# Switch-220v-HiLink-CC1101-AS07.net
KiCad netlist of a schematic drawn in EAGLE
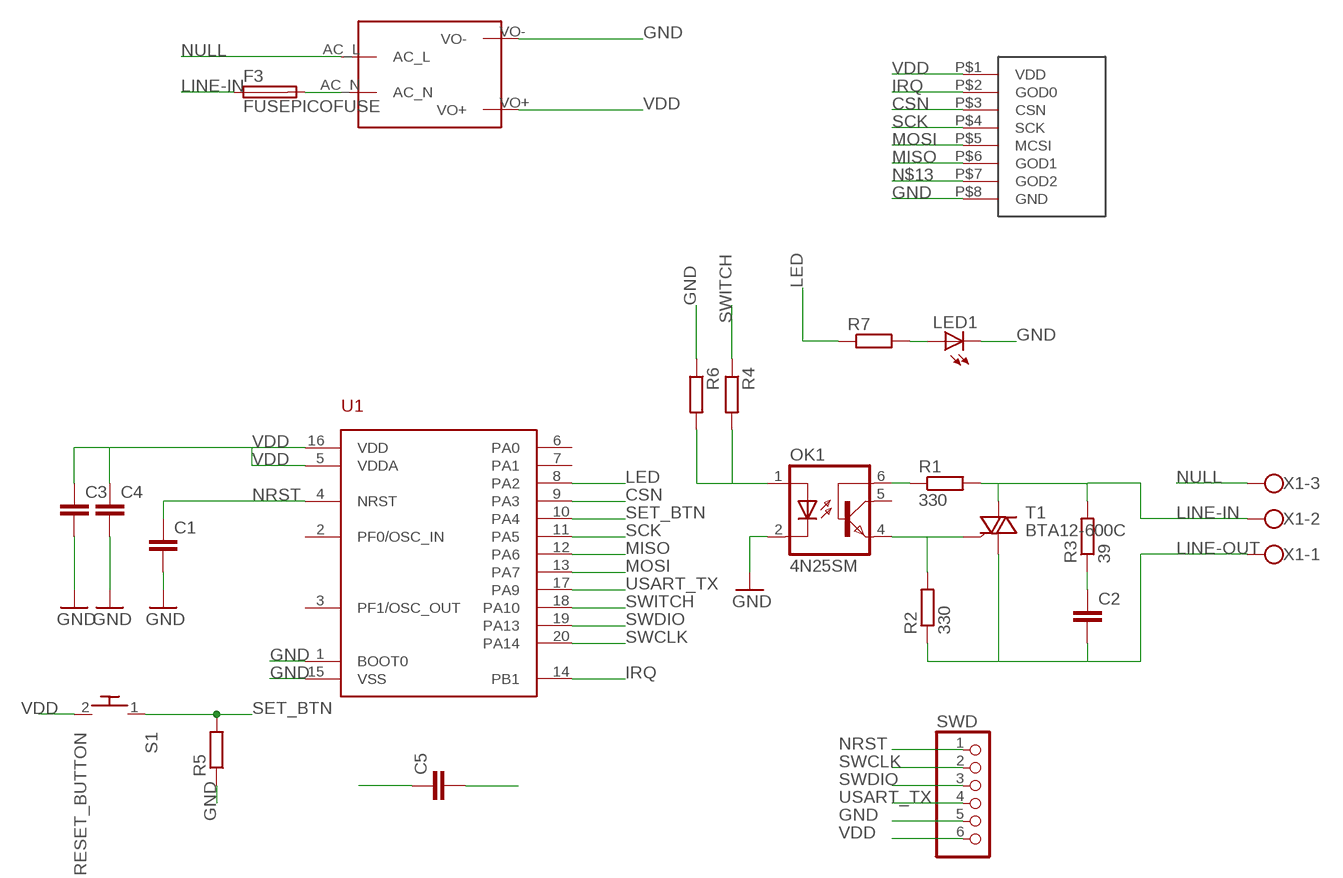
[diagram p0: schematic, sheet 1]

(export (version "E")
  (design (tool "Eeschema 10.0.6"))
  (components
    (comp (ref "C1")
      (value "C-EUC0805")
      (footprint "eagle-import:C0805")
      (libsource (lib "eagle-import") (part "C-EUC0805"))
    )
    (comp (ref "C2")
      (value "C-EU050-025X075")
      (footprint "eagle-import:C050-025X075")
      (libsource (lib "eagle-import") (part "C-EU050-025X075"))
    )
    (comp (ref "C3")
      (value "C-EUC0805")
      (footprint "eagle-import:C0805")
      (libsource (lib "eagle-import") (part "C-EUC0805"))
    )
    (comp (ref "C4")
      (value "C-EUC0805")
      (footprint "eagle-import:C0805")
      (libsource (lib "eagle-import") (part "C-EUC0805"))
    )
    (comp (ref "C5")
      (value "C-EUC0805")
      (footprint "eagle-import:C0805")
      (libsource (lib "eagle-import") (part "C-EUC0805"))
    )
    (comp (ref "F3")
      (value "FUSEPICOFUSE")
      (footprint "eagle-import:PICOFUSE")
      (libsource (lib "eagle-import") (part "FUSEPICOFUSE"))
    )
    (comp (ref "LED1")
      (value "LEDCHIP-LED0805")
      (footprint "eagle-import:CHIP-LED0805")
      (libsource (lib "eagle-import") (part "LEDCHIP-LED0805"))
    )
    (comp (ref "OK1")
      (value "4N25SM")
      (footprint "eagle-import:DIL6-SMD")
      (fields (field (name "MF") "FAIRCHILD SEMICONDUCTOR"))
      (libsource (lib "eagle-import") (part "4N?MS25"))
    )
    (comp (ref "R1")
      (value "330")
      (footprint "eagle-import:0207_2V")
      (libsource (lib "eagle-import") (part "R-EU_0207/2V"))
    )
    (comp (ref "R2")
      (value "330")
      (footprint "eagle-import:0204_7")
      (libsource (lib "eagle-import") (part "R-EU_0204/7"))
    )
    (comp (ref "R3")
      (value "39")
      (footprint "eagle-import:0204_7")
      (libsource (lib "eagle-import") (part "R-EU_0204/7"))
    )
    (comp (ref "R4")
      (value "R-EU_R0805")
      (footprint "eagle-import:R0805")
      (libsource (lib "eagle-import") (part "R-EU_R0805"))
    )
    (comp (ref "R5")
      (value "R-EU_R0805")
      (footprint "eagle-import:R0805")
      (libsource (lib "eagle-import") (part "R-EU_R0805"))
    )
    (comp (ref "R6")
      (value "R-EU_R0805")
      (footprint "eagle-import:R0805")
      (libsource (lib "eagle-import") (part "R-EU_R0805"))
    )
    (comp (ref "R7")
      (value "R-EU_R0805")
      (footprint "eagle-import:R0805")
      (libsource (lib "eagle-import") (part "R-EU_R0805"))
    )
    (comp (ref "S1")
      (value "RESET_BUTTON")
      (footprint "eagle-import:EVQ-PJU05K")
      (libsource (lib "eagle-import") (part "RESET_BUTTON"))
    )
    (comp (ref "SWD")
      (value "PINHD-1X6B")
      (footprint "eagle-import:1X06-BIG")
      (libsource (lib "eagle-import") (part "PINHD-1X6B"))
    )
    (comp (ref "T1")
      (value "BTA12-600C")
      (footprint "eagle-import:TO220DS")
      (libsource (lib "eagle-import") (part "BTA12-600C"))
    )
    (comp (ref "U$2")
      (value "MAINS_CONVERTERS")
      (footprint "eagle-import:HLK-PM01")
      (libsource (lib "eagle-import") (part "MAINS_CONVERTERS"))
    )
    (comp (ref "U$4")
      (value "AS07-M1101SSMD")
      (footprint "eagle-import:AS07-M1101S-SMD")
      (libsource (lib "eagle-import") (part "AS07-M1101SSMD"))
    )
    (comp (ref "U1")
      (value "STM32F030F4")
      (footprint "eagle-import:TSSOP20")
      (libsource (lib "eagle-import") (part "STM32F030F4"))
    )
    (comp (ref "X1")
      (value "W237-103")
      (footprint "eagle-import:W237-103")
      (fields (field (name "MPN") "237-103"))
      (libsource (lib "eagle-import") (part "W237-103"))
    )
  )
  (nets
    (net (code "1") (name "/CSN") (class "Default")
      (node (ref "U$4") (pin "P$3") (pinfunction "CSN_P$3") (pintype "bidirectional"))
      (node (ref "U1") (pin "9") (pinfunction "PA3_9") (pintype "bidirectional"))
    )
    (net (code "2") (name "/IRQ") (class "Default")
      (node (ref "U$4") (pin "P$2") (pinfunction "GOD0_P$2") (pintype "bidirectional"))
      (node (ref "U1") (pin "14") (pinfunction "PB1_14") (pintype "bidirectional"))
    )
    (net (code "3") (name "/LED") (class "Default")
      (node (ref "R7") (pin "1") (pinfunction "1_1") (pintype "passive"))
      (node (ref "U1") (pin "8") (pinfunction "PA2_8") (pintype "bidirectional"))
    )
    (net (code "4") (name "/LINE-IN") (class "Default")
      (node (ref "F3") (pin "1") (pinfunction "1_1") (pintype "passive"))
      (node (ref "R1") (pin "2") (pinfunction "2_2") (pintype "passive"))
      (node (ref "R3") (pin "2") (pinfunction "2_2") (pintype "passive"))
      (node (ref "T1") (pin "A2") (pinfunction "A2_A2") (pintype "passive"))
      (node (ref "X1") (pin "2") (pinfunction "KL_2") (pintype "passive"))
    )
    (net (code "5") (name "/LINE-OUT") (class "Default")
      (node (ref "C2") (pin "2") (pinfunction "2_2") (pintype "passive"))
      (node (ref "R2") (pin "1") (pinfunction "1_1") (pintype "passive"))
      (node (ref "T1") (pin "A1") (pinfunction "A1_A1") (pintype "passive"))
      (node (ref "X1") (pin "1") (pinfunction "KL_1") (pintype "passive"))
    )
    (net (code "6") (name "/MISO") (class "Default")
      (node (ref "U$4") (pin "P$6") (pinfunction "GOD1_P$6") (pintype "bidirectional"))
      (node (ref "U1") (pin "12") (pinfunction "PA6_12") (pintype "bidirectional"))
    )
    (net (code "7") (name "/MOSI") (class "Default")
      (node (ref "U$4") (pin "P$5") (pinfunction "MCSI_P$5") (pintype "bidirectional"))
      (node (ref "U1") (pin "13") (pinfunction "PA7_13") (pintype "bidirectional"))
    )
    (net (code "8") (name "/N$13") (class "Default")
      (node (ref "U$4") (pin "P$7") (pinfunction "GOD2_P$7") (pintype "bidirectional"))
    )
    (net (code "9") (name "/NRST") (class "Default")
      (node (ref "C1") (pin "1") (pinfunction "1_1") (pintype "passive"))
      (node (ref "SWD") (pin "1") (pinfunction "1_1") (pintype "passive"))
      (node (ref "U1") (pin "4") (pinfunction "NRST_4") (pintype "bidirectional"))
    )
    (net (code "10") (name "/NULL") (class "Default")
      (node (ref "U$2") (pin "AC_L") (pinfunction "AC_L_AC_L") (pintype "input"))
      (node (ref "X1") (pin "3") (pinfunction "KL_3") (pintype "passive"))
    )
    (net (code "11") (name "/SCK") (class "Default")
      (node (ref "U$4") (pin "P$4") (pinfunction "SCK_P$4") (pintype "bidirectional"))
      (node (ref "U1") (pin "11") (pinfunction "PA5_11") (pintype "bidirectional"))
    )
    (net (code "12") (name "/SET_BTN") (class "Default")
      (node (ref "R5") (pin "2") (pinfunction "2_2") (pintype "passive"))
      (node (ref "S1") (pin "1") (pinfunction "1_1") (pintype "passive"))
      (node (ref "U1") (pin "10") (pinfunction "PA4_10") (pintype "bidirectional"))
    )
    (net (code "13") (name "/SWCLK") (class "Default")
      (node (ref "SWD") (pin "2") (pinfunction "2_2") (pintype "passive"))
      (node (ref "U1") (pin "20") (pinfunction "PA14_20") (pintype "bidirectional"))
    )
    (net (code "14") (name "/SWDIO") (class "Default")
      (node (ref "SWD") (pin "3") (pinfunction "3_3") (pintype "passive"))
      (node (ref "U1") (pin "19") (pinfunction "PA13_19") (pintype "bidirectional"))
    )
    (net (code "15") (name "/SWITCH") (class "Default")
      (node (ref "R4") (pin "1") (pinfunction "1_1") (pintype "passive"))
      (node (ref "U1") (pin "18") (pinfunction "PA10_18") (pintype "bidirectional"))
    )
    (net (code "16") (name "/USART_TX") (class "Default")
      (node (ref "SWD") (pin "4") (pinfunction "4_4") (pintype "passive"))
      (node (ref "U1") (pin "17") (pinfunction "PA9_17") (pintype "bidirectional"))
    )
    (net (code "17") (name "/VDD") (class "Default")
      (node (ref "C3") (pin "1") (pinfunction "1_1") (pintype "passive"))
      (node (ref "C4") (pin "1") (pinfunction "1_1") (pintype "passive"))
      (node (ref "C5") (pin "2") (pinfunction "2_2") (pintype "passive"))
      (node (ref "S1") (pin "2") (pinfunction "2_2") (pintype "passive"))
      (node (ref "SWD") (pin "6") (pinfunction "6_6") (pintype "passive"))
      (node (ref "U$2") (pin "VO+") (pinfunction "VO+_VO+") (pintype "output"))
      (node (ref "U$4") (pin "P$1") (pinfunction "VDD_P$1") (pintype "bidirectional"))
      (node (ref "U1") (pin "16") (pinfunction "VDD_16") (pintype "bidirectional"))
      (node (ref "U1") (pin "5") (pinfunction "VDDA_5") (pintype "bidirectional"))
    )
    (net (code "18") (name "GND") (class "Default")
      (node (ref "C1") (pin "2") (pinfunction "2_2") (pintype "passive"))
      (node (ref "C3") (pin "2") (pinfunction "2_2") (pintype "passive"))
      (node (ref "C4") (pin "2") (pinfunction "2_2") (pintype "passive"))
      (node (ref "C5") (pin "1") (pinfunction "1_1") (pintype "passive"))
      (node (ref "LED1") (pin "C") (pinfunction "C_C") (pintype "passive"))
      (node (ref "OK1") (pin "2") (pinfunction "C_2") (pintype "passive"))
      (node (ref "R5") (pin "1") (pinfunction "1_1") (pintype "passive"))
      (node (ref "R6") (pin "1") (pinfunction "1_1") (pintype "passive"))
      (node (ref "SWD") (pin "5") (pinfunction "5_5") (pintype "passive"))
      (node (ref "U$2") (pin "VO-") (pinfunction "VO-_VO-") (pintype "output"))
      (node (ref "U$4") (pin "P$8") (pinfunction "GND_P$8") (pintype "bidirectional"))
      (node (ref "U1") (pin "1") (pinfunction "BOOT0_1") (pintype "bidirectional"))
      (node (ref "U1") (pin "15") (pinfunction "VSS_15") (pintype "bidirectional"))
    )
    (net (code "19") (name "Net-(C2-Pad1)") (class "Default")
      (node (ref "C2") (pin "1") (pinfunction "1_1") (pintype "passive"))
      (node (ref "R3") (pin "1") (pinfunction "1_1") (pintype "passive"))
    )
    (net (code "20") (name "Net-(F3-Pad2)") (class "Default")
      (node (ref "F3") (pin "2") (pinfunction "2_2") (pintype "passive"))
      (node (ref "U$2") (pin "AC_N") (pinfunction "AC_N_AC_N") (pintype "input"))
    )
    (net (code "21") (name "Net-(LED1-PadA)") (class "Default")
      (node (ref "LED1") (pin "A") (pinfunction "A_A") (pintype "passive"))
      (node (ref "R7") (pin "2") (pinfunction "2_2") (pintype "passive"))
    )
    (net (code "22") (name "Net-(OK1-A)") (class "Default")
      (node (ref "OK1") (pin "1") (pinfunction "A_1") (pintype "passive"))
      (node (ref "R4") (pin "2") (pinfunction "2_2") (pintype "passive"))
      (node (ref "R6") (pin "2") (pinfunction "2_2") (pintype "passive"))
    )
    (net (code "23") (name "Net-(OK1-BAS)") (class "Default")
      (node (ref "OK1") (pin "6") (pinfunction "BAS_6") (pintype "passive"))
      (node (ref "R1") (pin "1") (pinfunction "1_1") (pintype "passive"))
    )
    (net (code "24") (name "Net-(OK1-EMI)") (class "Default")
      (node (ref "OK1") (pin "4") (pinfunction "EMI_4") (pintype "passive"))
      (node (ref "R2") (pin "2") (pinfunction "2_2") (pintype "passive"))
      (node (ref "T1") (pin "G") (pinfunction "G_G") (pintype "passive"))
    )
    (net (code "25") (name "unconnected-(OK1-COL-Pad5)") (class "Default")
      (node (ref "OK1") (pin "5") (pinfunction "COL_5") (pintype "passive"))
    )
    (net (code "26") (name "unconnected-(U1-PA0-Pad6)") (class "Default")
      (node (ref "U1") (pin "6") (pinfunction "PA0_6") (pintype "bidirectional"))
    )
    (net (code "27") (name "unconnected-(U1-PA1-Pad7)") (class "Default")
      (node (ref "U1") (pin "7") (pinfunction "PA1_7") (pintype "bidirectional"))
    )
    (net (code "28") (name "unconnected-(U1-PF0{slash}OSC_IN-Pad2)") (class "Default")
      (node (ref "U1") (pin "2") (pinfunction "PF0/OSC_IN_2") (pintype "bidirectional"))
    )
    (net (code "29") (name "unconnected-(U1-PF1{slash}OSC_OUT-Pad3)") (class "Default")
      (node (ref "U1") (pin "3") (pinfunction "PF1/OSC_OUT_3") (pintype "bidirectional"))
    )
  )
)
